# Final_project_combined.net
KiCad netlist of a schematic drawn in EAGLE
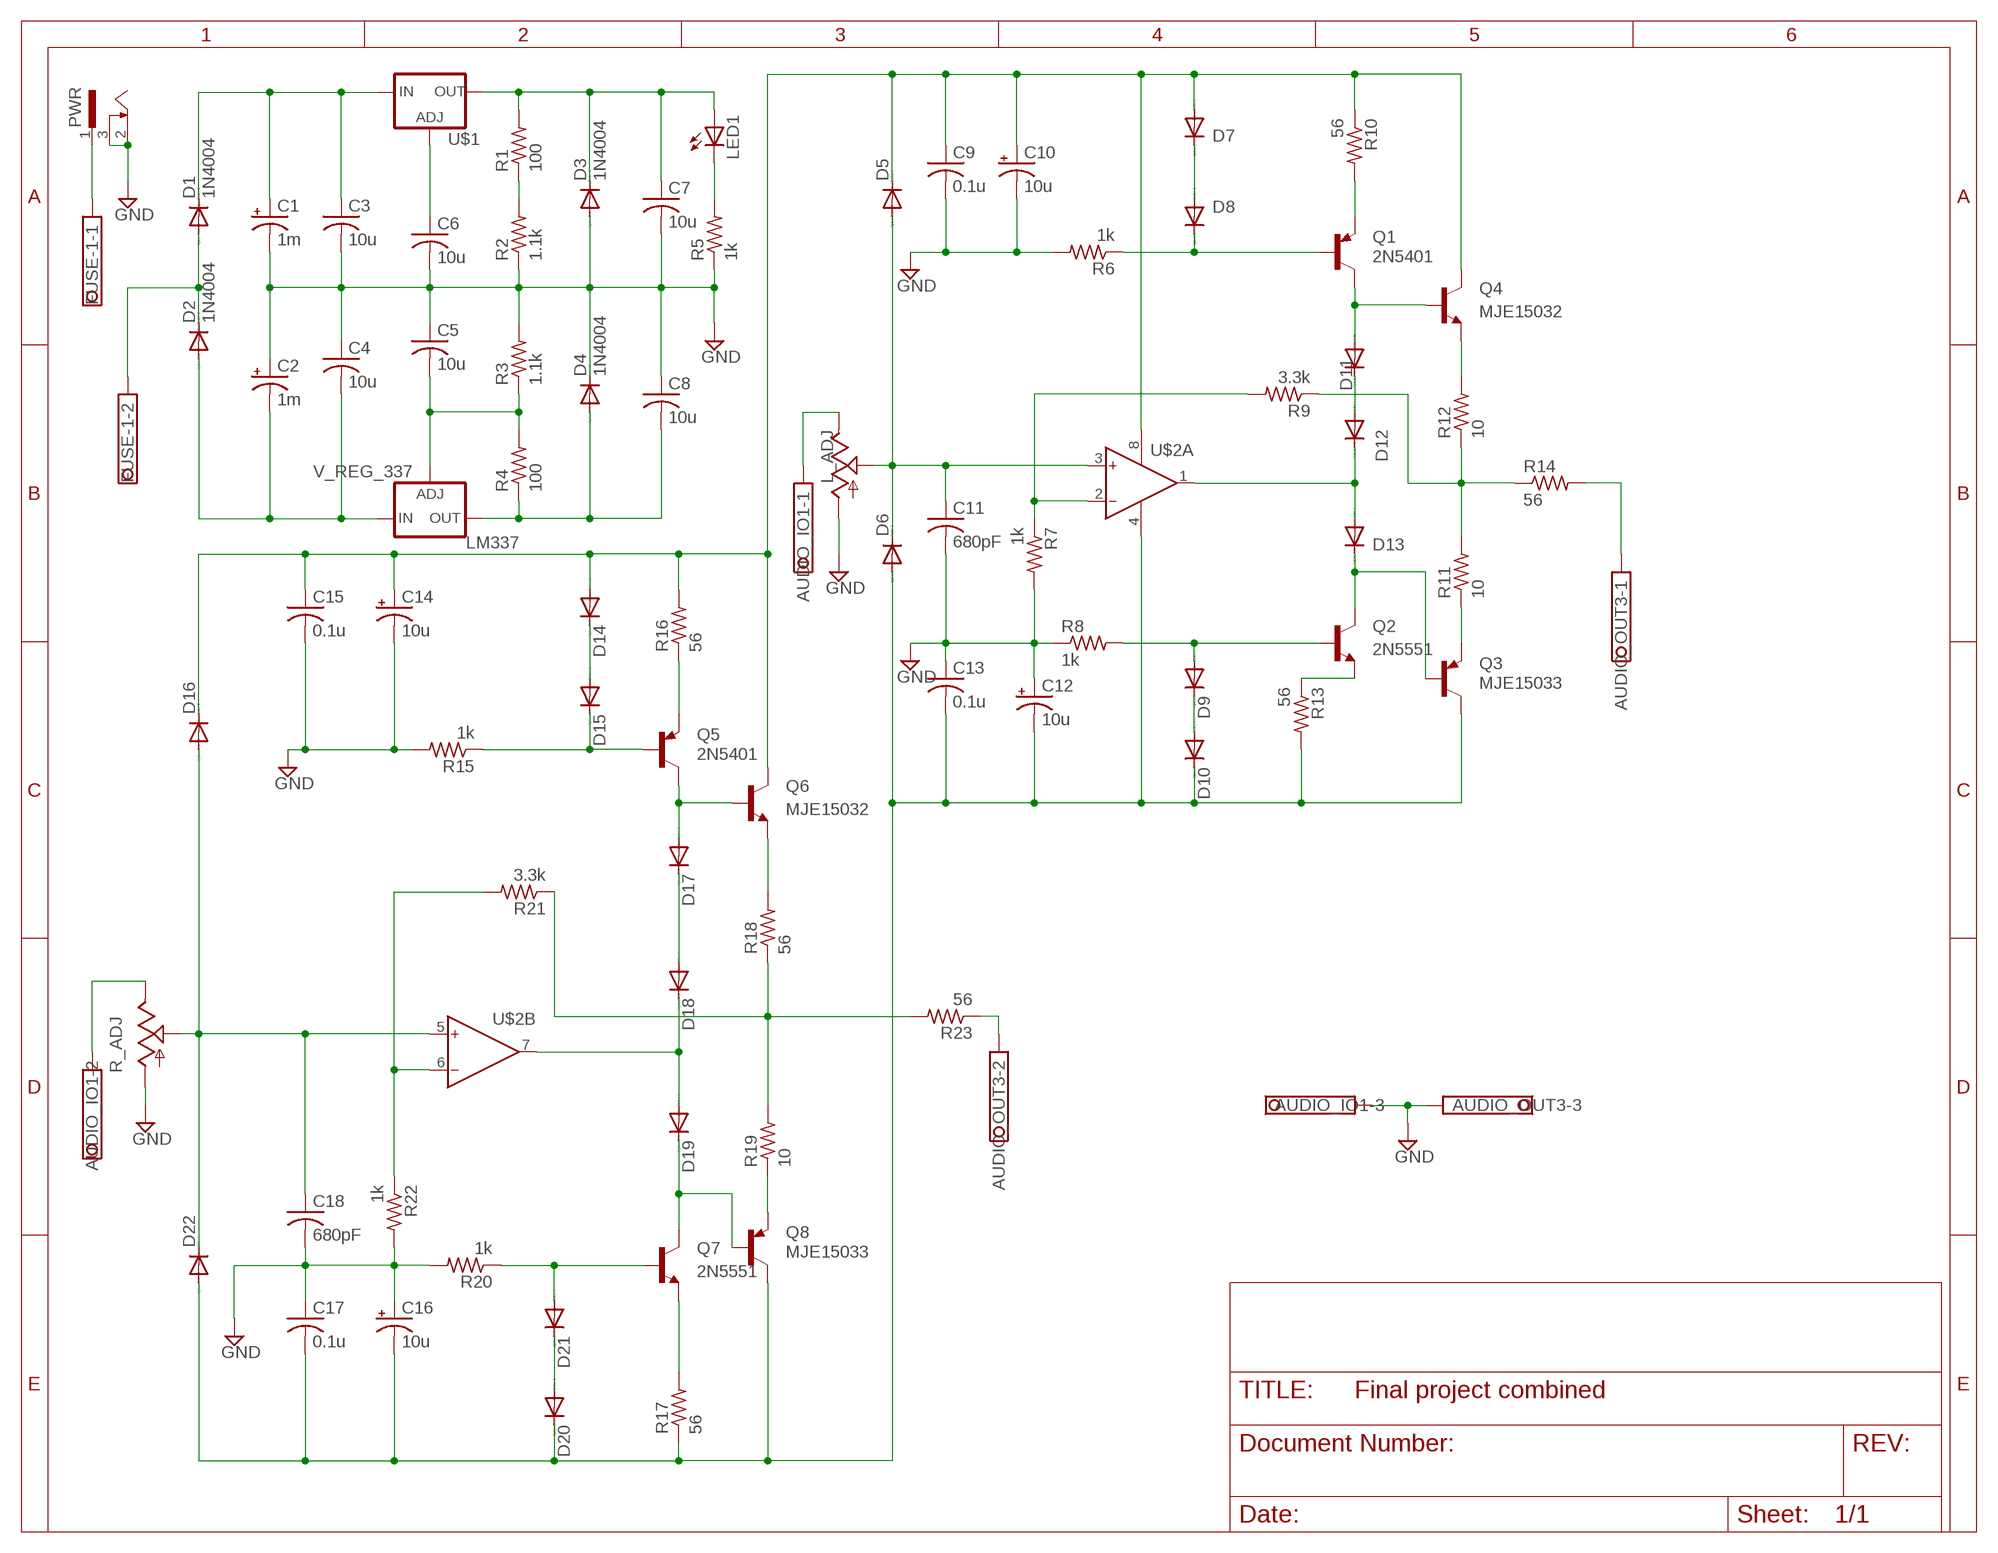
[diagram p0: schematic, sheet 1]

(export (version "E")
  (design (tool "Eeschema 10.0.6"))
  (components
    (comp (ref "AUDIO_IO1")
      (value "1751251")
      (footprint "eagle-import:1751251")
      (libsource (lib "eagle-import") (part "1751251"))
    )
    (comp (ref "AUDIO_OUT3")
      (value "1751251")
      (footprint "eagle-import:1751251")
      (libsource (lib "eagle-import") (part "1751251"))
    )
    (comp (ref "C1")
      (value "1m")
      (footprint "eagle-import:E2-5")
      (libsource (lib "eagle-import") (part "CPOL-USE2-5"))
    )
    (comp (ref "C2")
      (value "1m")
      (footprint "eagle-import:E2-5")
      (libsource (lib "eagle-import") (part "CPOL-USE2-5"))
    )
    (comp (ref "C3")
      (value "10u")
      (footprint "eagle-import:C025-024X044")
      (libsource (lib "eagle-import") (part "C-US025-024X044"))
    )
    (comp (ref "C4")
      (value "10u")
      (footprint "eagle-import:C025-024X044")
      (libsource (lib "eagle-import") (part "C-US025-024X044"))
    )
    (comp (ref "C5")
      (value "10u")
      (footprint "eagle-import:C025-024X044")
      (libsource (lib "eagle-import") (part "C-US025-024X044"))
    )
    (comp (ref "C6")
      (value "10u")
      (footprint "eagle-import:C025-024X044")
      (libsource (lib "eagle-import") (part "C-US025-024X044"))
    )
    (comp (ref "C7")
      (value "10u")
      (footprint "eagle-import:C025-024X044")
      (libsource (lib "eagle-import") (part "C-US025-024X044"))
    )
    (comp (ref "C8")
      (value "10u")
      (footprint "eagle-import:C025-024X044")
      (libsource (lib "eagle-import") (part "C-US025-024X044"))
    )
    (comp (ref "C9")
      (value "0.1u")
      (footprint "eagle-import:C025-024X044")
      (libsource (lib "eagle-import") (part "C-US025-024X044"))
    )
    (comp (ref "C10")
      (value "10u")
      (footprint "eagle-import:E2-5")
      (libsource (lib "eagle-import") (part "CPOL-USE2-5"))
    )
    (comp (ref "C11")
      (value "680pF")
      (footprint "eagle-import:C025-024X044")
      (libsource (lib "eagle-import") (part "C-US025-024X044"))
    )
    (comp (ref "C12")
      (value "10u")
      (footprint "eagle-import:E2-5")
      (libsource (lib "eagle-import") (part "CPOL-USE2-5"))
    )
    (comp (ref "C13")
      (value "0.1u")
      (footprint "eagle-import:C025-024X044")
      (libsource (lib "eagle-import") (part "C-US025-024X044"))
    )
    (comp (ref "C14")
      (value "10u")
      (footprint "eagle-import:E2-5")
      (libsource (lib "eagle-import") (part "CPOL-USE2-5"))
    )
    (comp (ref "C15")
      (value "0.1u")
      (footprint "eagle-import:C025-024X044")
      (libsource (lib "eagle-import") (part "C-US025-024X044"))
    )
    (comp (ref "C16")
      (value "10u")
      (footprint "eagle-import:E2-5")
      (libsource (lib "eagle-import") (part "CPOL-USE2-5"))
    )
    (comp (ref "C17")
      (value "0.1u")
      (footprint "eagle-import:C025-024X044")
      (libsource (lib "eagle-import") (part "C-US025-024X044"))
    )
    (comp (ref "C18")
      (value "680pF")
      (footprint "eagle-import:C025-024X044")
      (libsource (lib "eagle-import") (part "C-US025-024X044"))
    )
    (comp (ref "D1")
      (value "1N4004")
      (footprint "eagle-import:DO41-10")
      (libsource (lib "eagle-import") (part "1N4004"))
    )
    (comp (ref "D2")
      (value "1N4004")
      (footprint "eagle-import:DO41-10")
      (libsource (lib "eagle-import") (part "1N4004"))
    )
    (comp (ref "D3")
      (value "1N4004")
      (footprint "eagle-import:DO41-10")
      (libsource (lib "eagle-import") (part "1N4004"))
    )
    (comp (ref "D4")
      (value "1N4004")
      (footprint "eagle-import:DO41-10")
      (libsource (lib "eagle-import") (part "1N4004"))
    )
    (comp (ref "D5")
      (value "1N4148DO35-7")
      (footprint "eagle-import:DO35-7")
      (libsource (lib "eagle-import") (part "1N4148DO35-7"))
    )
    (comp (ref "D6")
      (value "1N4148DO35-7")
      (footprint "eagle-import:DO35-7")
      (libsource (lib "eagle-import") (part "1N4148DO35-7"))
    )
    (comp (ref "D7")
      (value "1N4148DO35-7")
      (footprint "eagle-import:DO35-7")
      (libsource (lib "eagle-import") (part "1N4148DO35-7"))
    )
    (comp (ref "D8")
      (value "1N4148DO35-7")
      (footprint "eagle-import:DO35-7")
      (libsource (lib "eagle-import") (part "1N4148DO35-7"))
    )
    (comp (ref "D9")
      (value "1N4148DO35-7")
      (footprint "eagle-import:DO35-7")
      (libsource (lib "eagle-import") (part "1N4148DO35-7"))
    )
    (comp (ref "D10")
      (value "1N4148DO35-7")
      (footprint "eagle-import:DO35-7")
      (libsource (lib "eagle-import") (part "1N4148DO35-7"))
    )
    (comp (ref "D11")
      (value "1N4148DO35-7")
      (footprint "eagle-import:DO35-7")
      (libsource (lib "eagle-import") (part "1N4148DO35-7"))
    )
    (comp (ref "D12")
      (value "1N4148DO35-7")
      (footprint "eagle-import:DO35-7")
      (libsource (lib "eagle-import") (part "1N4148DO35-7"))
    )
    (comp (ref "D13")
      (value "1N4148DO35-7")
      (footprint "eagle-import:DO35-7")
      (libsource (lib "eagle-import") (part "1N4148DO35-7"))
    )
    (comp (ref "D14")
      (value "1N4004")
      (footprint "eagle-import:DO41-10")
      (libsource (lib "eagle-import") (part "1N4004"))
    )
    (comp (ref "D15")
      (value "1N4004")
      (footprint "eagle-import:DO41-10")
      (libsource (lib "eagle-import") (part "1N4004"))
    )
    (comp (ref "D16")
      (value "1N4004")
      (footprint "eagle-import:DO41-10")
      (libsource (lib "eagle-import") (part "1N4004"))
    )
    (comp (ref "D17")
      (value "1N4004")
      (footprint "eagle-import:DO41-10")
      (libsource (lib "eagle-import") (part "1N4004"))
    )
    (comp (ref "D18")
      (value "1N4004")
      (footprint "eagle-import:DO41-10")
      (libsource (lib "eagle-import") (part "1N4004"))
    )
    (comp (ref "D19")
      (value "1N4004")
      (footprint "eagle-import:DO41-10")
      (libsource (lib "eagle-import") (part "1N4004"))
    )
    (comp (ref "D20")
      (value "1N4004")
      (footprint "eagle-import:DO41-10")
      (libsource (lib "eagle-import") (part "1N4004"))
    )
    (comp (ref "D21")
      (value "1N4004")
      (footprint "eagle-import:DO41-10")
      (libsource (lib "eagle-import") (part "1N4004"))
    )
    (comp (ref "D22")
      (value "1N4004")
      (footprint "eagle-import:DO41-10")
      (libsource (lib "eagle-import") (part "1N4004"))
    )
    (comp (ref "FUSE-1")
      (value "1751248")
      (footprint "eagle-import:1751248")
      (libsource (lib "eagle-import") (part "1751248"))
    )
    (comp (ref "LED1")
      (value "LED5MM")
      (footprint "eagle-import:LED5MM")
      (libsource (lib "eagle-import") (part "LED5MM"))
    )
    (comp (ref "LM337")
      (value "V_REG_337")
      (footprint "eagle-import:TO220-ADJ-NEG")
      (libsource (lib "eagle-import") (part "V_REG_337"))
    )
    (comp (ref "L_ADJ")
      (value "TRIM_US-B64Y")
      (footprint "eagle-import:B64Y")
      (libsource (lib "eagle-import") (part "TRIM_US-B64Y"))
    )
    (comp (ref "PWR")
      (value "SCD-014A")
      (footprint "eagle-import:SCD-014-A")
      (libsource (lib "eagle-import") (part "SCD-014A"))
    )
    (comp (ref "Q1")
      (value "2N5401")
      (footprint "eagle-import:2N5401")
      (libsource (lib "eagle-import") (part "2N5401"))
    )
    (comp (ref "Q2")
      (value "2N5551")
      (footprint "eagle-import:2N5551")
      (libsource (lib "eagle-import") (part "2N5551"))
    )
    (comp (ref "Q3")
      (value "MJE15033")
      (footprint "eagle-import:TO220V")
      (libsource (lib "eagle-import") (part "MJE15033"))
    )
    (comp (ref "Q4")
      (value "MJE15032")
      (footprint "eagle-import:TO220V")
      (libsource (lib "eagle-import") (part "MJE15032"))
    )
    (comp (ref "Q5")
      (value "2N5401")
      (footprint "eagle-import:2N5401")
      (libsource (lib "eagle-import") (part "2N5401"))
    )
    (comp (ref "Q6")
      (value "MJE15032")
      (footprint "eagle-import:TO220V")
      (libsource (lib "eagle-import") (part "MJE15032"))
    )
    (comp (ref "Q7")
      (value "2N5551")
      (footprint "eagle-import:2N5551")
      (libsource (lib "eagle-import") (part "2N5551"))
    )
    (comp (ref "Q8")
      (value "MJE15033")
      (footprint "eagle-import:TO220V")
      (libsource (lib "eagle-import") (part "MJE15033"))
    )
    (comp (ref "R1")
      (value "100")
      (footprint "eagle-import:0207_15")
      (libsource (lib "eagle-import") (part "R-US_0207/15"))
    )
    (comp (ref "R2")
      (value "1.1k")
      (footprint "eagle-import:0207_15")
      (libsource (lib "eagle-import") (part "R-US_0207/15"))
    )
    (comp (ref "R3")
      (value "1.1k")
      (footprint "eagle-import:0207_15")
      (libsource (lib "eagle-import") (part "R-US_0207/15"))
    )
    (comp (ref "R4")
      (value "100")
      (footprint "eagle-import:0207_15")
      (libsource (lib "eagle-import") (part "R-US_0207/15"))
    )
    (comp (ref "R5")
      (value "1k")
      (footprint "eagle-import:0207_15")
      (libsource (lib "eagle-import") (part "R-US_0207/15"))
    )
    (comp (ref "R6")
      (value "1k")
      (footprint "eagle-import:0207_15")
      (libsource (lib "eagle-import") (part "R-US_0207/15"))
    )
    (comp (ref "R7")
      (value "1k")
      (footprint "eagle-import:0207_15")
      (libsource (lib "eagle-import") (part "R-US_0207/15"))
    )
    (comp (ref "R8")
      (value "1k")
      (footprint "eagle-import:0207_15")
      (libsource (lib "eagle-import") (part "R-US_0207/15"))
    )
    (comp (ref "R9")
      (value "3.3k")
      (footprint "eagle-import:0207_15")
      (libsource (lib "eagle-import") (part "R-US_0207/15"))
    )
    (comp (ref "R10")
      (value "56")
      (footprint "eagle-import:0207_15")
      (libsource (lib "eagle-import") (part "R-US_0207/15"))
    )
    (comp (ref "R11")
      (value "10")
      (footprint "eagle-import:0207_15")
      (libsource (lib "eagle-import") (part "R-US_0207/15"))
    )
    (comp (ref "R12")
      (value "10")
      (footprint "eagle-import:0207_15")
      (libsource (lib "eagle-import") (part "R-US_0207/15"))
    )
    (comp (ref "R13")
      (value "56")
      (footprint "eagle-import:0207_15")
      (libsource (lib "eagle-import") (part "R-US_0207/15"))
    )
    (comp (ref "R14")
      (value "56")
      (footprint "eagle-import:0207_15")
      (libsource (lib "eagle-import") (part "R-US_0207/15"))
    )
    (comp (ref "R15")
      (value "1k")
      (footprint "eagle-import:0207_15")
      (libsource (lib "eagle-import") (part "R-US_0207/15"))
    )
    (comp (ref "R16")
      (value "56")
      (footprint "eagle-import:0207_15")
      (libsource (lib "eagle-import") (part "R-US_0207/15"))
    )
    (comp (ref "R17")
      (value "56")
      (footprint "eagle-import:0207_15")
      (libsource (lib "eagle-import") (part "R-US_0207/15"))
    )
    (comp (ref "R18")
      (value "56")
      (footprint "eagle-import:0207_15")
      (libsource (lib "eagle-import") (part "R-US_0207/15"))
    )
    (comp (ref "R19")
      (value "10")
      (footprint "eagle-import:0207_15")
      (libsource (lib "eagle-import") (part "R-US_0207/15"))
    )
    (comp (ref "R20")
      (value "1k")
      (footprint "eagle-import:0207_15")
      (libsource (lib "eagle-import") (part "R-US_0207/15"))
    )
    (comp (ref "R21")
      (value "3.3k")
      (footprint "eagle-import:0207_15")
      (libsource (lib "eagle-import") (part "R-US_0207/15"))
    )
    (comp (ref "R22")
      (value "1k")
      (footprint "eagle-import:0207_15")
      (libsource (lib "eagle-import") (part "R-US_0207/15"))
    )
    (comp (ref "R23")
      (value "56")
      (footprint "eagle-import:0207_15")
      (libsource (lib "eagle-import") (part "R-US_0207/15"))
    )
    (comp (ref "R_ADJ")
      (value "TRIM_US-B64Y")
      (footprint "eagle-import:B64Y")
      (libsource (lib "eagle-import") (part "TRIM_US-B64Y"))
    )
    (comp (ref "U$1")
      (value "V_REG_317SINK")
      (footprint "eagle-import:TO220-ADJ")
      (libsource (lib "eagle-import") (part "V_REG_317SINK"))
    )
    (comp (ref "U$2")
      (value "OP275'P'")
      (footprint "eagle-import:DIL08")
      (libsource (lib "eagle-import") (part "OP275'P'"))
    )
  )
  (nets
    (net (code "1") (name "GND") (class "Default")
      (node (ref "AUDIO_IO1") (pin "3") (pinfunction "K_3") (pintype "passive"))
      (node (ref "AUDIO_OUT3") (pin "3") (pinfunction "K_3") (pintype "passive"))
      (node (ref "C1") (pin "-") (pinfunction "-_-") (pintype "passive"))
      (node (ref "C10") (pin "-") (pinfunction "-_-") (pintype "passive"))
      (node (ref "C11") (pin "2") (pinfunction "2_2") (pintype "passive"))
      (node (ref "C12") (pin "+") (pinfunction "+_+") (pintype "passive"))
      (node (ref "C13") (pin "1") (pinfunction "1_1") (pintype "passive"))
      (node (ref "C14") (pin "-") (pinfunction "-_-") (pintype "passive"))
      (node (ref "C15") (pin "2") (pinfunction "2_2") (pintype "passive"))
      (node (ref "C16") (pin "+") (pinfunction "+_+") (pintype "passive"))
      (node (ref "C17") (pin "1") (pinfunction "1_1") (pintype "passive"))
      (node (ref "C18") (pin "2") (pinfunction "2_2") (pintype "passive"))
      (node (ref "C2") (pin "+") (pinfunction "+_+") (pintype "passive"))
      (node (ref "C3") (pin "2") (pinfunction "2_2") (pintype "passive"))
      (node (ref "C4") (pin "1") (pinfunction "1_1") (pintype "passive"))
      (node (ref "C5") (pin "1") (pinfunction "1_1") (pintype "passive"))
      (node (ref "C6") (pin "2") (pinfunction "2_2") (pintype "passive"))
      (node (ref "C7") (pin "2") (pinfunction "2_2") (pintype "passive"))
      (node (ref "C8") (pin "1") (pinfunction "1_1") (pintype "passive"))
      (node (ref "C9") (pin "2") (pinfunction "2_2") (pintype "passive"))
      (node (ref "D3") (pin "A") (pinfunction "A_A") (pintype "passive"))
      (node (ref "D4") (pin "C") (pinfunction "C_C") (pintype "passive"))
      (node (ref "L_ADJ") (pin "A") (pinfunction "A_A") (pintype "passive"))
      (node (ref "PWR") (pin "2") (pinfunction "2_2") (pintype "passive"))
      (node (ref "PWR") (pin "3") (pinfunction "3_3") (pintype "passive"))
      (node (ref "R15") (pin "2") (pinfunction "2_2") (pintype "passive"))
      (node (ref "R2") (pin "1") (pinfunction "1_1") (pintype "passive"))
      (node (ref "R20") (pin "2") (pinfunction "2_2") (pintype "passive"))
      (node (ref "R22") (pin "2") (pinfunction "2_2") (pintype "passive"))
      (node (ref "R3") (pin "2") (pinfunction "2_2") (pintype "passive"))
      (node (ref "R5") (pin "1") (pinfunction "1_1") (pintype "passive"))
      (node (ref "R6") (pin "2") (pinfunction "2_2") (pintype "passive"))
      (node (ref "R7") (pin "2") (pinfunction "2_2") (pintype "passive"))
      (node (ref "R8") (pin "1") (pinfunction "1_1") (pintype "passive"))
      (node (ref "R_ADJ") (pin "A") (pinfunction "A_A") (pintype "passive"))
    )
    (net (code "2") (name "Net-(AUDIO_IO1A-K)") (class "Default")
      (node (ref "AUDIO_IO1") (pin "1") (pinfunction "K_1") (pintype "passive"))
      (node (ref "L_ADJ") (pin "E") (pinfunction "E_E") (pintype "passive"))
    )
    (net (code "3") (name "Net-(AUDIO_IO1B-K)") (class "Default")
      (node (ref "AUDIO_IO1") (pin "2") (pinfunction "K_2") (pintype "passive"))
      (node (ref "R_ADJ") (pin "E") (pinfunction "E_E") (pintype "passive"))
    )
    (net (code "4") (name "Net-(AUDIO_OUT3A-K)") (class "Default")
      (node (ref "AUDIO_OUT3") (pin "1") (pinfunction "K_1") (pintype "passive"))
      (node (ref "R14") (pin "2") (pinfunction "2_2") (pintype "passive"))
    )
    (net (code "5") (name "Net-(AUDIO_OUT3B-K)") (class "Default")
      (node (ref "AUDIO_OUT3") (pin "2") (pinfunction "K_2") (pintype "passive"))
      (node (ref "R23") (pin "1") (pinfunction "1_1") (pintype "passive"))
    )
    (net (code "6") (name "Net-(C1-Pad+)") (class "Default")
      (node (ref "C1") (pin "+") (pinfunction "+_+") (pintype "passive"))
      (node (ref "C3") (pin "1") (pinfunction "1_1") (pintype "passive"))
      (node (ref "D1") (pin "C") (pinfunction "C_C") (pintype "passive"))
      (node (ref "U$1") (pin "IN") (pinfunction "IN_IN") (pintype "input"))
    )
    (net (code "7") (name "Net-(C2-Pad-)") (class "Default")
      (node (ref "C2") (pin "-") (pinfunction "-_-") (pintype "passive"))
      (node (ref "C4") (pin "2") (pinfunction "2_2") (pintype "passive"))
      (node (ref "D2") (pin "A") (pinfunction "A_A") (pintype "passive"))
      (node (ref "LM337") (pin "IN") (pinfunction "IN_IN") (pintype "input"))
    )
    (net (code "8") (name "Net-(C5-Pad2)") (class "Default")
      (node (ref "C5") (pin "2") (pinfunction "2_2") (pintype "passive"))
      (node (ref "LM337") (pin "ADJ") (pinfunction "ADJ_ADJ") (pintype "input"))
      (node (ref "R3") (pin "1") (pinfunction "1_1") (pintype "passive"))
      (node (ref "R4") (pin "2") (pinfunction "2_2") (pintype "passive"))
    )
    (net (code "9") (name "Net-(C6-Pad1)") (class "Default")
      (node (ref "C6") (pin "1") (pinfunction "1_1") (pintype "passive"))
      (node (ref "U$1") (pin "ADJ") (pinfunction "ADJ_ADJ") (pintype "input"))
    )
    (net (code "10") (name "Net-(C7-Pad1)") (class "Default")
      (node (ref "C7") (pin "1") (pinfunction "1_1") (pintype "passive"))
      (node (ref "D3") (pin "C") (pinfunction "C_C") (pintype "passive"))
      (node (ref "LED1") (pin "A") (pinfunction "A_A") (pintype "passive"))
      (node (ref "R1") (pin "2") (pinfunction "2_2") (pintype "passive"))
      (node (ref "U$1") (pin "OUT") (pinfunction "OUT_OUT") (pintype "output"))
    )
    (net (code "11") (name "Net-(C8-Pad2)") (class "Default")
      (node (ref "C8") (pin "2") (pinfunction "2_2") (pintype "passive"))
      (node (ref "D4") (pin "A") (pinfunction "A_A") (pintype "passive"))
      (node (ref "LM337") (pin "OUT") (pinfunction "OUT_OUT") (pintype "output"))
      (node (ref "R4") (pin "1") (pinfunction "1_1") (pintype "passive"))
    )
    (net (code "12") (name "Net-(D7-PadC)") (class "Default")
      (node (ref "D7") (pin "C") (pinfunction "C_C") (pintype "passive"))
      (node (ref "D8") (pin "A") (pinfunction "A_A") (pintype "passive"))
    )
    (net (code "13") (name "Net-(D8-PadC)") (class "Default")
      (node (ref "D8") (pin "C") (pinfunction "C_C") (pintype "passive"))
      (node (ref "Q1") (pin "B") (pinfunction "B_B") (pintype "passive"))
      (node (ref "R6") (pin "1") (pinfunction "1_1") (pintype "passive"))
    )
    (net (code "14") (name "Net-(D9-PadA)") (class "Default")
      (node (ref "D9") (pin "A") (pinfunction "A_A") (pintype "passive"))
      (node (ref "Q2") (pin "B") (pinfunction "B_B") (pintype "passive"))
      (node (ref "R8") (pin "2") (pinfunction "2_2") (pintype "passive"))
    )
    (net (code "15") (name "Net-(D10-PadA)") (class "Default")
      (node (ref "D10") (pin "A") (pinfunction "A_A") (pintype "passive"))
      (node (ref "D9") (pin "C") (pinfunction "C_C") (pintype "passive"))
    )
    (net (code "16") (name "Net-(D11-PadC)") (class "Default")
      (node (ref "D11") (pin "C") (pinfunction "C_C") (pintype "passive"))
      (node (ref "D12") (pin "A") (pinfunction "A_A") (pintype "passive"))
    )
    (net (code "17") (name "Net-(D14-PadC)") (class "Default")
      (node (ref "D14") (pin "C") (pinfunction "C_C") (pintype "passive"))
      (node (ref "D15") (pin "A") (pinfunction "A_A") (pintype "passive"))
    )
    (net (code "18") (name "Net-(D15-PadC)") (class "Default")
      (node (ref "D15") (pin "C") (pinfunction "C_C") (pintype "passive"))
      (node (ref "Q5") (pin "B") (pinfunction "B_B") (pintype "passive"))
      (node (ref "R15") (pin "1") (pinfunction "1_1") (pintype "passive"))
    )
    (net (code "19") (name "Net-(D17-PadC)") (class "Default")
      (node (ref "D17") (pin "C") (pinfunction "C_C") (pintype "passive"))
      (node (ref "D18") (pin "A") (pinfunction "A_A") (pintype "passive"))
    )
    (net (code "20") (name "Net-(D20-PadA)") (class "Default")
      (node (ref "D20") (pin "A") (pinfunction "A_A") (pintype "passive"))
      (node (ref "D21") (pin "C") (pinfunction "C_C") (pintype "passive"))
    )
    (net (code "21") (name "Net-(D21-PadA)") (class "Default")
      (node (ref "D21") (pin "A") (pinfunction "A_A") (pintype "passive"))
      (node (ref "Q7") (pin "B") (pinfunction "B_B") (pintype "passive"))
      (node (ref "R20") (pin "1") (pinfunction "1_1") (pintype "passive"))
    )
    (net (code "22") (name "Net-(FUSE-1A-K)") (class "Default")
      (node (ref "FUSE-1") (pin "1") (pinfunction "K_1") (pintype "passive"))
      (node (ref "PWR") (pin "1") (pinfunction "1_1") (pintype "passive"))
    )
    (net (code "23") (name "Net-(FUSE-1B-K)") (class "Default")
      (node (ref "D1") (pin "A") (pinfunction "A_A") (pintype "passive"))
      (node (ref "D2") (pin "C") (pinfunction "C_C") (pintype "passive"))
      (node (ref "FUSE-1") (pin "2") (pinfunction "K_2") (pintype "passive"))
    )
    (net (code "24") (name "Net-(LED1-C)") (class "Default")
      (node (ref "LED1") (pin "K") (pinfunction "C_K") (pintype "passive"))
      (node (ref "R5") (pin "2") (pinfunction "2_2") (pintype "passive"))
    )
    (net (code "25") (name "Net-(Q1-PadE)") (class "Default")
      (node (ref "Q1") (pin "E") (pinfunction "E_E") (pintype "passive"))
      (node (ref "R10") (pin "2") (pinfunction "2_2") (pintype "passive"))
    )
    (net (code "26") (name "Net-(Q2-PadE)") (class "Default")
      (node (ref "Q2") (pin "E") (pinfunction "E_E") (pintype "passive"))
      (node (ref "R13") (pin "1") (pinfunction "1_1") (pintype "passive"))
    )
    (net (code "27") (name "Net-(Q3-B)") (class "Default")
      (node (ref "D13") (pin "C") (pinfunction "C_C") (pintype "passive"))
      (node (ref "Q2") (pin "C") (pinfunction "C_C") (pintype "passive"))
      (node (ref "Q3") (pin "1") (pinfunction "B_1") (pintype "passive"))
    )
    (net (code "28") (name "Net-(Q3-C)") (class "Default")
      (node (ref "C12") (pin "-") (pinfunction "-_-") (pintype "passive"))
      (node (ref "C13") (pin "2") (pinfunction "2_2") (pintype "passive"))
      (node (ref "C16") (pin "-") (pinfunction "-_-") (pintype "passive"))
      (node (ref "C17") (pin "2") (pinfunction "2_2") (pintype "passive"))
      (node (ref "D10") (pin "C") (pinfunction "C_C") (pintype "passive"))
      (node (ref "D20") (pin "C") (pinfunction "C_C") (pintype "passive"))
      (node (ref "D22") (pin "A") (pinfunction "A_A") (pintype "passive"))
      (node (ref "D6") (pin "A") (pinfunction "A_A") (pintype "passive"))
      (node (ref "Q3") (pin "2") (pinfunction "C_2") (pintype "passive"))
      (node (ref "Q8") (pin "2") (pinfunction "C_2") (pintype "passive"))
      (node (ref "R13") (pin "2") (pinfunction "2_2") (pintype "passive"))
      (node (ref "R17") (pin "1") (pinfunction "1_1") (pintype "passive"))
      (node (ref "U$2") (pin "4") (pinfunction "V-_4") (pintype "power_in"))
    )
    (net (code "29") (name "Net-(Q3-E)") (class "Default")
      (node (ref "Q3") (pin "3") (pinfunction "E_3") (pintype "passive"))
      (node (ref "R11") (pin "1") (pinfunction "1_1") (pintype "passive"))
    )
    (net (code "30") (name "Net-(Q4-B)") (class "Default")
      (node (ref "D11") (pin "A") (pinfunction "A_A") (pintype "passive"))
      (node (ref "Q1") (pin "C") (pinfunction "C_C") (pintype "passive"))
      (node (ref "Q4") (pin "1") (pinfunction "B_1") (pintype "passive"))
    )
    (net (code "31") (name "Net-(Q4-C)") (class "Default")
      (node (ref "C10") (pin "+") (pinfunction "+_+") (pintype "passive"))
      (node (ref "C14") (pin "+") (pinfunction "+_+") (pintype "passive"))
      (node (ref "C15") (pin "1") (pinfunction "1_1") (pintype "passive"))
      (node (ref "C9") (pin "1") (pinfunction "1_1") (pintype "passive"))
      (node (ref "D14") (pin "A") (pinfunction "A_A") (pintype "passive"))
      (node (ref "D16") (pin "C") (pinfunction "C_C") (pintype "passive"))
      (node (ref "D5") (pin "C") (pinfunction "C_C") (pintype "passive"))
      (node (ref "D7") (pin "A") (pinfunction "A_A") (pintype "passive"))
      (node (ref "Q4") (pin "2") (pinfunction "C_2") (pintype "passive"))
      (node (ref "Q6") (pin "2") (pinfunction "C_2") (pintype "passive"))
      (node (ref "R10") (pin "1") (pinfunction "1_1") (pintype "passive"))
      (node (ref "R16") (pin "2") (pinfunction "2_2") (pintype "passive"))
      (node (ref "U$2") (pin "8") (pinfunction "V+_8") (pintype "power_in"))
    )
    (net (code "32") (name "Net-(Q4-E)") (class "Default")
      (node (ref "Q4") (pin "3") (pinfunction "E_3") (pintype "passive"))
      (node (ref "R12") (pin "2") (pinfunction "2_2") (pintype "passive"))
    )
    (net (code "33") (name "Net-(Q5-PadE)") (class "Default")
      (node (ref "Q5") (pin "E") (pinfunction "E_E") (pintype "passive"))
      (node (ref "R16") (pin "1") (pinfunction "1_1") (pintype "passive"))
    )
    (net (code "34") (name "Net-(Q6-B)") (class "Default")
      (node (ref "D17") (pin "A") (pinfunction "A_A") (pintype "passive"))
      (node (ref "Q5") (pin "C") (pinfunction "C_C") (pintype "passive"))
      (node (ref "Q6") (pin "1") (pinfunction "B_1") (pintype "passive"))
    )
    (net (code "35") (name "Net-(Q6-E)") (class "Default")
      (node (ref "Q6") (pin "3") (pinfunction "E_3") (pintype "passive"))
      (node (ref "R18") (pin "2") (pinfunction "2_2") (pintype "passive"))
    )
    (net (code "36") (name "Net-(Q7-PadE)") (class "Default")
      (node (ref "Q7") (pin "E") (pinfunction "E_E") (pintype "passive"))
      (node (ref "R17") (pin "2") (pinfunction "2_2") (pintype "passive"))
    )
    (net (code "37") (name "Net-(Q8-B)") (class "Default")
      (node (ref "D19") (pin "C") (pinfunction "C_C") (pintype "passive"))
      (node (ref "Q7") (pin "C") (pinfunction "C_C") (pintype "passive"))
      (node (ref "Q8") (pin "1") (pinfunction "B_1") (pintype "passive"))
    )
    (net (code "38") (name "Net-(Q8-E)") (class "Default")
      (node (ref "Q8") (pin "3") (pinfunction "E_3") (pintype "passive"))
      (node (ref "R19") (pin "1") (pinfunction "1_1") (pintype "passive"))
    )
    (net (code "39") (name "Net-(R1-Pad1)") (class "Default")
      (node (ref "R1") (pin "1") (pinfunction "1_1") (pintype "passive"))
      (node (ref "R2") (pin "2") (pinfunction "2_2") (pintype "passive"))
    )
    (net (code "40") (name "Net-(R11-Pad2)") (class "Default")
      (node (ref "R11") (pin "2") (pinfunction "2_2") (pintype "passive"))
      (node (ref "R12") (pin "1") (pinfunction "1_1") (pintype "passive"))
      (node (ref "R14") (pin "1") (pinfunction "1_1") (pintype "passive"))
      (node (ref "R9") (pin "1") (pinfunction "1_1") (pintype "passive"))
    )
    (net (code "41") (name "Net-(R18-Pad1)") (class "Default")
      (node (ref "R18") (pin "1") (pinfunction "1_1") (pintype "passive"))
      (node (ref "R19") (pin "2") (pinfunction "2_2") (pintype "passive"))
      (node (ref "R21") (pin "1") (pinfunction "1_1") (pintype "passive"))
      (node (ref "R23") (pin "2") (pinfunction "2_2") (pintype "passive"))
    )
    (net (code "42") (name "Net-(U$2A-IN+)") (class "Default")
      (node (ref "C11") (pin "1") (pinfunction "1_1") (pintype "passive"))
      (node (ref "D5") (pin "A") (pinfunction "A_A") (pintype "passive"))
      (node (ref "D6") (pin "C") (pinfunction "C_C") (pintype "passive"))
      (node (ref "L_ADJ") (pin "S") (pinfunction "S_S") (pintype "passive"))
      (node (ref "U$2") (pin "3") (pinfunction "IN+_3") (pintype "input"))
    )
    (net (code "43") (name "Net-(U$2A-IN-)") (class "Default")
      (node (ref "R7") (pin "1") (pinfunction "1_1") (pintype "passive"))
      (node (ref "R9") (pin "2") (pinfunction "2_2") (pintype "passive"))
      (node (ref "U$2") (pin "2") (pinfunction "IN-_2") (pintype "input"))
    )
    (net (code "44") (name "Net-(U$2A-OUT)") (class "Default")
      (node (ref "D12") (pin "C") (pinfunction "C_C") (pintype "passive"))
      (node (ref "D13") (pin "A") (pinfunction "A_A") (pintype "passive"))
      (node (ref "U$2") (pin "1") (pinfunction "OUT_1") (pintype "output"))
    )
    (net (code "45") (name "Net-(U$2B-IN+)") (class "Default")
      (node (ref "C18") (pin "1") (pinfunction "1_1") (pintype "passive"))
      (node (ref "D16") (pin "A") (pinfunction "A_A") (pintype "passive"))
      (node (ref "D22") (pin "C") (pinfunction "C_C") (pintype "passive"))
      (node (ref "R_ADJ") (pin "S") (pinfunction "S_S") (pintype "passive"))
      (node (ref "U$2") (pin "5") (pinfunction "IN+_5") (pintype "input"))
    )
    (net (code "46") (name "Net-(U$2B-IN-)") (class "Default")
      (node (ref "R21") (pin "2") (pinfunction "2_2") (pintype "passive"))
      (node (ref "R22") (pin "1") (pinfunction "1_1") (pintype "passive"))
      (node (ref "U$2") (pin "6") (pinfunction "IN-_6") (pintype "input"))
    )
    (net (code "47") (name "Net-(U$2B-OUT)") (class "Default")
      (node (ref "D18") (pin "C") (pinfunction "C_C") (pintype "passive"))
      (node (ref "D19") (pin "A") (pinfunction "A_A") (pintype "passive"))
      (node (ref "U$2") (pin "7") (pinfunction "OUT_7") (pintype "output"))
    )
  )
)
